# Over_current.net
KiCad netlist of a schematic drawn in Altium Designer
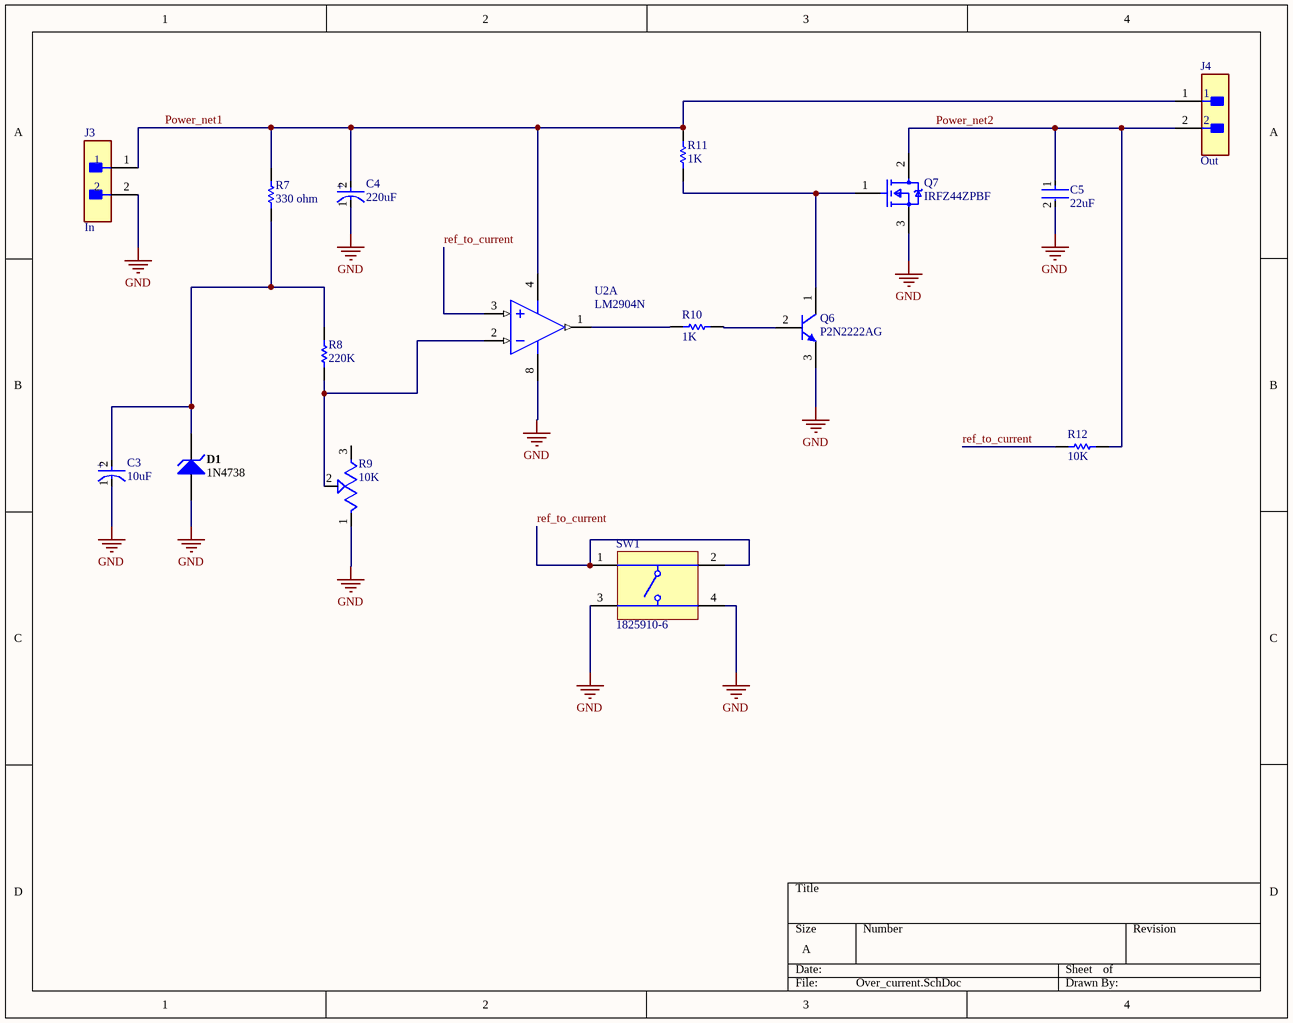
[diagram p0: Over_current.SchDoc]

(export (version "E")
  (design (tool "Eeschema 10.0.6"))
  (components
    (comp (ref "C3")
      (value "10uF")
      (footprint "FP-RAD-TH-D_10_0_5-L_20_2-MFG")
      (description "Aluminum Electrolytic Capacitors (Radial Lead Type) 10uF ±20% 400V")
      (fields (field (name "VOLTAGE") "400V") (field (name "TOLERANCE") "20%"))
      (libsource (lib "Altium Content Vault") (part "203bc49f2ac43e59fd269a8c329ed05"))
    )
    (comp (ref "C4")
      (value "220uF")
      (footprint "FP-RAD-TH-D_10_0_5-L_20_2-MFG")
      (description "Aluminum Electrolytic Capacitors (Radial Lead Type) 10uF ±20% 400V")
      (fields (field (name "VOLTAGE") "400V") (field (name "TOLERANCE") "20%"))
      (libsource (lib "Altium Content Vault") (part "203bc49f2ac43e59fd269a8c329ed05"))
    )
    (comp (ref "C5")
      (value "22uF")
      (footprint "FP-RCEWM1-MFG")
      (description "CAP CER 22UF 25V X7R RADIAL")
      (fields (field (name "TOLERANCE") "20%"))
      (libsource (lib "Altium Content Vault") (part "02cd4be3c70576c341d710602a673aa"))
    )
    (comp (ref "D1")
      (value "1N4738")
      (footprint "FAIR-DO-41-2_V")
      (description "Zener Diode, 4.7V, 1W, 5%, -65 to 200 degC, 2-Pin DO-41, Body 2.72 x 5.2 mm, RoHS")
      (fields (field (name "PARTNUMBER") "1N4732A") (field (name "TOLERANCE") "5%"))
      (libsource (lib "Altium Content Vault") (part "FAIR-DZEN-A1K2-2"))
    )
    (comp (ref "J3")
      (value "In")
      (footprint "FP-B2B-XH-A_LF_SN-MFG")
      (description "CONN HEADER VERT 2POS 2.5MM")
      (libsource (lib "") (part "3bc925449376181038e59eaffc5286c_1"))
    )
    (comp (ref "J4")
      (value "Out")
      (footprint "FP-B2B-XH-A_LF_SN-MFG")
      (description "CONN HEADER VERT 2POS 2.5MM")
      (libsource (lib "Altium Content Vault") (part "3bc925449376181038e59eaffc5286c"))
    )
    (comp (ref "Q6")
      (value "P2N2222AG")
      (footprint "ONSC-TO-92-3-29-11")
      (description "Amplifier Transistor, NPN Silicon, 3-Pin TO-92, Pb-Free, Bulk Box")
      (fields (field (name "MANUFACTURER") "On Semiconductor"))
      (libsource (lib "Altium Content Vault") (part "ONSC-NPN-C1B2E3-3"))
    )
    (comp (ref "Q7")
      (value "IRFZ44ZPBF")
      (footprint "FP-PG-TO220-3-MFG")
      (description "MOSFET N-CH 55V 51A TO220AB")
      (libsource (lib "Altium Content Vault") (part "b09f7f152735e370c1ea22a33fa83d6"))
    )
    (comp (ref "R7")
      (value "330 ohm")
      (footprint "OMTE-WLA-2_V2")
      (description "Miniature Wirewound Current Sense, 0.02 Ohm +/-1%, 0.5 W, 2-Pin THD, RoHS, 25pc Pack")
      (fields (field (name "PARTNUMBER") "WLAR020FE") (field (name "MANUFACTURER") "Ohmite"))
      (libsource (lib "Altium Content Vault") (part "OMTE-RES-2"))
    )
    (comp (ref "R8")
      (value "220K")
      (footprint "OMTE-WLA-2_V2")
      (description "Miniature Wirewound Current Sense, 0.02 Ohm +/-1%, 0.5 W, 2-Pin THD, RoHS, 25pc Pack")
      (fields (field (name "PARTNUMBER") "WLAR020FE") (field (name "MANUFACTURER") "Ohmite"))
      (libsource (lib "Altium Content Vault") (part "OMTE-RES-2"))
    )
    (comp (ref "R9")
      (value "10K")
      (footprint "TRIM_3306F-1-104")
      (description "100 kOhms 0.2W, 1/5W PC Pins Through Hole Trimmer Potentiometer Cermet 1 Turn Top Adjustment")
      (fields (field (name "MP") "3306F-1-104") (field (name "MF") "Bourns"))
      (libsource (lib "Schlib1") (part "3306F-1-104"))
    )
    (comp (ref "R10")
      (value "1K")
      (footprint "OMTE-WLA-2_V2")
      (description "Miniature Wirewound Current Sense, 0.02 Ohm +/-1%, 0.5 W, 2-Pin THD, RoHS, 25pc Pack")
      (fields (field (name "PARTNUMBER") "WLAR020FE") (field (name "MANUFACTURER") "Ohmite"))
      (libsource (lib "Altium Content Vault") (part "OMTE-RES-2"))
    )
    (comp (ref "R11")
      (value "1K")
      (footprint "OMTE-WLA-2_V2")
      (description "Miniature Wirewound Current Sense, 0.02 Ohm +/-1%, 0.5 W, 2-Pin THD, RoHS, 25pc Pack")
      (fields (field (name "PARTNUMBER") "WLAR020FE") (field (name "MANUFACTURER") "Ohmite"))
      (libsource (lib "Altium Content Vault") (part "OMTE-RES-2"))
    )
    (comp (ref "R12")
      (value "10K")
      (footprint "OMTE-WLA-2_V2")
      (description "Miniature Wirewound Current Sense, 0.02 Ohm +/-1%, 0.5 W, 2-Pin THD, RoHS, 25pc Pack")
      (fields (field (name "PARTNUMBER") "WLAR020FE") (field (name "MANUFACTURER") "Ohmite"))
      (libsource (lib "Altium Content Vault") (part "OMTE-RES-2"))
    )
    (comp (ref "SW1")
      (value "1825910-6")
      (footprint "TECO-1825910-6_V")
      (description "Tact Switch, SPST-NO, 0.05 A, -35 to 85 degC, 4-Pin THD, RoHS, Bulk")
      (fields (field (name "MANUFACTURER") "TE Connectivity"))
      (libsource (lib "Altium Content Vault") (part "SW-SPST-4_A"))
    )
    (comp (ref "U2")
      (value "LM2904N")
      (footprint "ONSC-PDIP-8-626-05_M")
      (description "Single Supply Dual Operational Amplifier, 3 to 32 V, -40 to 105 degC, 8-Pin PDIP, Tube")
      (fields (field (name "MANUFACTURER") "On Semiconductor"))
      (libsource (lib "Altium Content Vault") (part "ONSC-LM258_2904-8"))
    )
  )
  (nets
    (net (code "1") (name "/Power_net1") (class "Default")
      (node (ref "C4") (pin "2") (pinfunction "A_2") (pintype "passive"))
      (node (ref "J3") (pin "1") (pinfunction "1_1") (pintype "passive"))
      (node (ref "J4") (pin "1") (pinfunction "1_1") (pintype "passive"))
      (node (ref "R11") (pin "1") (pinfunction "1_1") (pintype "passive"))
      (node (ref "R7") (pin "2") (pinfunction "2_2") (pintype "passive"))
      (node (ref "U2") (pin "4") (pinfunction "VEE/GND_4") (pintype "power_in"))
    )
    (net (code "2") (name "/Power_net2") (class "Default")
      (node (ref "C5") (pin "1") (pinfunction "1_1") (pintype "passive"))
      (node (ref "J4") (pin "2") (pinfunction "2_2") (pintype "passive"))
      (node (ref "Q7") (pin "2") (pinfunction "D_2") (pintype "passive"))
      (node (ref "R12") (pin "1") (pinfunction "1_1") (pintype "passive"))
    )
    (net (code "3") (name "/ref_to_current") (class "Default")
      (node (ref "R12") (pin "2") (pinfunction "2_2") (pintype "passive"))
      (node (ref "SW1") (pin "1") (pinfunction "1_1") (pintype "passive"))
      (node (ref "SW1") (pin "2") (pinfunction "2_2") (pintype "passive"))
      (node (ref "U2") (pin "3") (pinfunction "INA+_3") (pintype "input"))
    )
    (net (code "4") (name "GND") (class "Default")
      (node (ref "C3") (pin "1") (pinfunction "C_1") (pintype "passive"))
      (node (ref "C4") (pin "1") (pinfunction "C_1") (pintype "passive"))
      (node (ref "C5") (pin "2") (pinfunction "2_2") (pintype "passive"))
      (node (ref "D1") (pin "1") (pinfunction "A_1") (pintype "passive"))
      (node (ref "J3") (pin "2") (pinfunction "2_2") (pintype "passive"))
      (node (ref "Q6") (pin "3") (pinfunction "E_3") (pintype "passive"))
      (node (ref "Q7") (pin "3") (pinfunction "S_3") (pintype "passive"))
      (node (ref "R9") (pin "1") (pinfunction "CCW_1") (pintype "passive"))
      (node (ref "SW1") (pin "3") (pinfunction "3_3") (pintype "passive"))
      (node (ref "SW1") (pin "4") (pinfunction "4_4") (pintype "passive"))
      (node (ref "U2") (pin "8") (pinfunction "VCC_8") (pintype "power_in"))
    )
    (net (code "5") (name "Net-(C3-A)") (class "Default")
      (node (ref "C3") (pin "2") (pinfunction "A_2") (pintype "passive"))
      (node (ref "D1") (pin "2") (pinfunction "K_2") (pintype "passive"))
      (node (ref "R7") (pin "1") (pinfunction "1_1") (pintype "passive"))
      (node (ref "R8") (pin "2") (pinfunction "2_2") (pintype "passive"))
    )
    (net (code "6") (name "Net-(Q6-B)") (class "Default")
      (node (ref "Q6") (pin "2") (pinfunction "B_2") (pintype "passive"))
      (node (ref "R10") (pin "1") (pinfunction "1_1") (pintype "passive"))
    )
    (net (code "7") (name "Net-(Q6-C)") (class "Default")
      (node (ref "Q6") (pin "1") (pinfunction "C_1") (pintype "passive"))
      (node (ref "Q7") (pin "1") (pinfunction "G_1") (pintype "passive"))
      (node (ref "R11") (pin "2") (pinfunction "2_2") (pintype "passive"))
    )
    (net (code "8") (name "Net-(R9-W)") (class "Default")
      (node (ref "R8") (pin "1") (pinfunction "1_1") (pintype "passive"))
      (node (ref "R9") (pin "2") (pinfunction "W_2") (pintype "passive"))
      (node (ref "U2") (pin "2") (pinfunction "INA-_2") (pintype "input"))
    )
    (net (code "9") (name "Net-(U2A-OUTA)") (class "Default")
      (node (ref "R10") (pin "2") (pinfunction "2_2") (pintype "passive"))
      (node (ref "U2") (pin "1") (pinfunction "OUTA_1") (pintype "output"))
    )
    (net (code "10") (name "unconnected-(R9-CW-Pad3)") (class "Default")
      (node (ref "R9") (pin "3") (pinfunction "CW_3") (pintype "passive"))
    )
  )
)
